# program_counter.net
KiCad netlist of a schematic drawn in Altium Designer
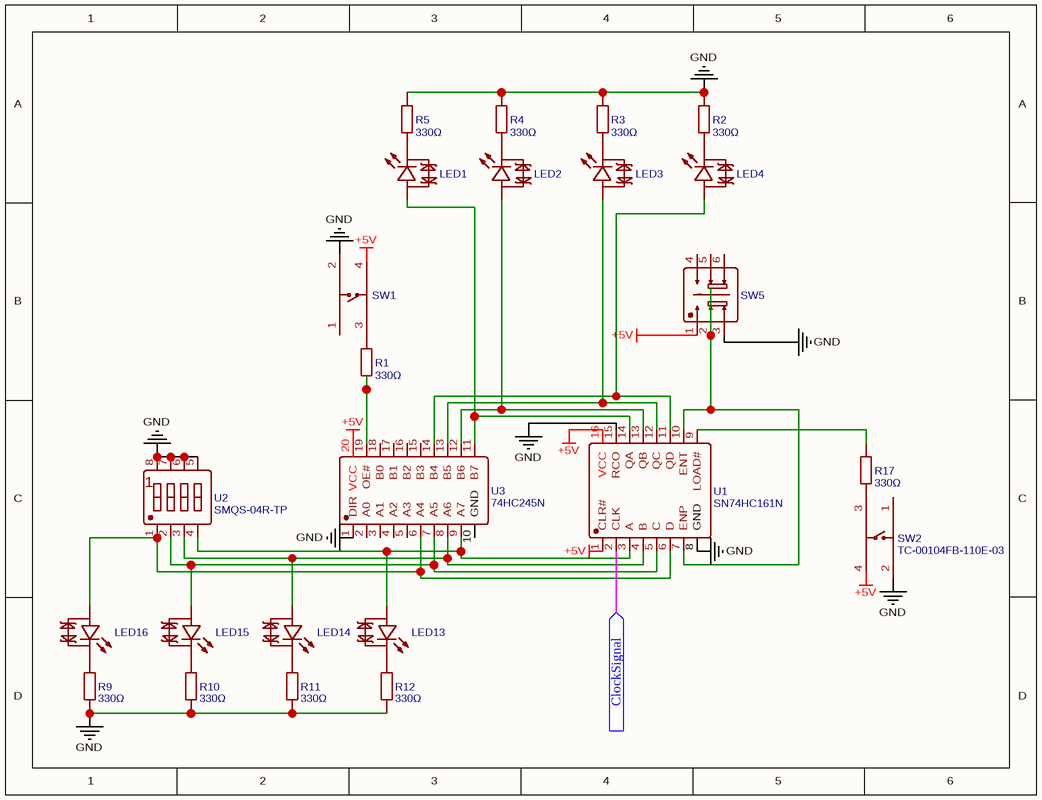
[diagram p0: program_counter.schdoc]

(export (version "E")
  (design (tool "Eeschema 10.0.6"))
  (components
    (comp (ref "LED1")
      (value "204-15UTC/S400-X9-L")
      (fields (field (name "MANUFACTURER") "EVERLIGHT(亿光)") (field (name "CONTRIBUTOR") "LCSC"))
      (libsource (lib "altium-import") (part "root_1_204-15UTC/S400-X9-L_"))
    )
    (comp (ref "LED2")
      (value "204-15UTC/S400-X9-L")
      (fields (field (name "MANUFACTURER") "EVERLIGHT(亿光)") (field (name "CONTRIBUTOR") "LCSC"))
      (libsource (lib "altium-import") (part "root_1_204-15UTC/S400-X9-L_"))
    )
    (comp (ref "LED3")
      (value "204-15UTC/S400-X9-L")
      (fields (field (name "MANUFACTURER") "EVERLIGHT(亿光)") (field (name "CONTRIBUTOR") "LCSC"))
      (libsource (lib "altium-import") (part "root_1_204-15UTC/S400-X9-L_"))
    )
    (comp (ref "LED4")
      (value "204-15UTC/S400-X9-L")
      (fields (field (name "MANUFACTURER") "EVERLIGHT(亿光)") (field (name "CONTRIBUTOR") "LCSC"))
      (libsource (lib "altium-import") (part "root_1_204-15UTC/S400-X9-L_"))
    )
    (comp (ref "LED13")
      (value "204-15UTC/S400-X9-L")
      (fields (field (name "MANUFACTURER") "EVERLIGHT(亿光)") (field (name "CONTRIBUTOR") "LCSC"))
      (libsource (lib "altium-import") (part "root_3_204-15UTC/S400-X9-L_"))
    )
    (comp (ref "LED14")
      (value "204-15UTC/S400-X9-L")
      (fields (field (name "MANUFACTURER") "EVERLIGHT(亿光)") (field (name "CONTRIBUTOR") "LCSC"))
      (libsource (lib "altium-import") (part "root_3_204-15UTC/S400-X9-L_"))
    )
    (comp (ref "LED15")
      (value "204-15UTC/S400-X9-L")
      (fields (field (name "MANUFACTURER") "EVERLIGHT(亿光)") (field (name "CONTRIBUTOR") "LCSC"))
      (libsource (lib "altium-import") (part "root_3_204-15UTC/S400-X9-L_"))
    )
    (comp (ref "LED16")
      (value "204-15UTC/S400-X9-L")
      (fields (field (name "MANUFACTURER") "EVERLIGHT(亿光)") (field (name "CONTRIBUTOR") "LCSC"))
      (libsource (lib "altium-import") (part "root_3_204-15UTC/S400-X9-L_"))
    )
    (comp (ref "R1")
      (value "330Ω")
      (fields
        (field (name "MANUFACTURER") "CCO(千志电子)")
        (field (name "MANUFACTURER PART") "MF1/2W-0.1Ω±1% T")
        (field (name "CONTRIBUTOR") "LCSC")
      )
      (libsource (lib "altium-import") (part "root_1_330Ω_"))
    )
    (comp (ref "R2")
      (value "330Ω")
      (fields
        (field (name "MANUFACTURER") "CCO(千志电子)")
        (field (name "MANUFACTURER PART") "MF1/2W-0.1Ω±1% T")
        (field (name "CONTRIBUTOR") "LCSC")
      )
      (libsource (lib "altium-import") (part "root_1_330Ω_"))
    )
    (comp (ref "R3")
      (value "330Ω")
      (fields
        (field (name "MANUFACTURER") "CCO(千志电子)")
        (field (name "MANUFACTURER PART") "MF1/2W-0.1Ω±1% T")
        (field (name "CONTRIBUTOR") "LCSC")
      )
      (libsource (lib "altium-import") (part "root_1_330Ω_"))
    )
    (comp (ref "R4")
      (value "330Ω")
      (fields
        (field (name "MANUFACTURER") "CCO(千志电子)")
        (field (name "MANUFACTURER PART") "MF1/2W-0.1Ω±1% T")
        (field (name "CONTRIBUTOR") "LCSC")
      )
      (libsource (lib "altium-import") (part "root_1_330Ω_"))
    )
    (comp (ref "R5")
      (value "330Ω")
      (fields
        (field (name "MANUFACTURER") "CCO(千志电子)")
        (field (name "MANUFACTURER PART") "MF1/2W-0.1Ω±1% T")
        (field (name "CONTRIBUTOR") "LCSC")
      )
      (libsource (lib "altium-import") (part "root_1_330Ω_"))
    )
    (comp (ref "R9")
      (value "330Ω")
      (fields
        (field (name "MANUFACTURER") "CCO(千志电子)")
        (field (name "MANUFACTURER PART") "MF1/2W-0.1Ω±1% T")
        (field (name "CONTRIBUTOR") "LCSC")
      )
      (libsource (lib "altium-import") (part "root_3_330Ω_"))
    )
    (comp (ref "R10")
      (value "330Ω")
      (fields
        (field (name "MANUFACTURER") "CCO(千志电子)")
        (field (name "MANUFACTURER PART") "MF1/2W-0.1Ω±1% T")
        (field (name "CONTRIBUTOR") "LCSC")
      )
      (libsource (lib "altium-import") (part "root_3_330Ω_"))
    )
    (comp (ref "R11")
      (value "330Ω")
      (fields
        (field (name "MANUFACTURER") "CCO(千志电子)")
        (field (name "MANUFACTURER PART") "MF1/2W-0.1Ω±1% T")
        (field (name "CONTRIBUTOR") "LCSC")
      )
      (libsource (lib "altium-import") (part "root_3_330Ω_"))
    )
    (comp (ref "R12")
      (value "330Ω")
      (fields
        (field (name "MANUFACTURER") "CCO(千志电子)")
        (field (name "MANUFACTURER PART") "MF1/2W-0.1Ω±1% T")
        (field (name "CONTRIBUTOR") "LCSC")
      )
      (libsource (lib "altium-import") (part "root_3_330Ω_"))
    )
    (comp (ref "R17")
      (value "330Ω")
      (fields
        (field (name "MANUFACTURER") "CCO(千志电子)")
        (field (name "MANUFACTURER PART") "MF1/2W-0.1Ω±1% T")
        (field (name "CONTRIBUTOR") "LCSC")
      )
      (libsource (lib "altium-import") (part "root_3_330Ω_"))
    )
    (comp (ref "SW1")
      (value "TC-00104FB-110E-03")
      (fields (field (name "MANUFACTURER") "HOOYA(皓宇电子)") (field (name "CONTRIBUTOR") "lcsc"))
      (libsource (lib "altium-import") (part "root_1_TC-00104FB-110E-03_"))
    )
    (comp (ref "SW2")
      (value "TC-00104FB-110E-03")
      (fields (field (name "MANUFACTURER") "HOOYA(皓宇电子)") (field (name "CONTRIBUTOR") "lcsc"))
      (libsource (lib "altium-import") (part "root_3_TC-00104FB-110E-03_"))
    )
    (comp (ref "SW5")
      (value "XKB8585-Z-190")
      (fields (field (name "MANUFACTURER") "XKB Connectivity(中国星坤)") (field (name "CONTRIBUTOR") "LCSC"))
      (libsource (lib "altium-import") (part "root_1_XKB8585-Z-190_"))
    )
    (comp (ref "U1")
      (value "SN74HC161N")
      (fields (field (name "MANUFACTURER") "TI(德州仪器)") (field (name "CONTRIBUTOR") "lcsc"))
      (libsource (lib "altium-import") (part "root_1_SN74HC161N_"))
    )
    (comp (ref "U2")
      (value "SMQS-04R-TP")
      (fields (field (name "MANUFACTURER") "SM Switch") (field (name "CONTRIBUTOR") "lcsc"))
      (libsource (lib "altium-import") (part "root_1_SMQS-04R-TP_"))
    )
    (comp (ref "U3")
      (value "74HC245N")
      (fields (field (name "MANUFACTURER") "HGSEMI(华冠)") (field (name "CONTRIBUTOR") "LCSC"))
      (libsource (lib "altium-import") (part "root_1_74HC245N_"))
    )
  )
  (nets
    (net (code "1") (name "+5V") (class "Default")
      (node (ref "SW5") (pin "1") (pinfunction "1_1") (pintype "passive"))
      (node (ref "U1") (pin "1") (pinfunction "CLR#_1") (pintype "passive"))
      (node (ref "U1") (pin "16") (pinfunction "VCC_16") (pintype "passive"))
      (node (ref "U3") (pin "20") (pinfunction "VCC_20") (pintype "passive"))
    )
    (net (code "2") (name "/ClockSignal") (class "Default")
      (node (ref "U1") (pin "2") (pinfunction "CLK_2") (pintype "passive"))
    )
    (net (code "3") (name "GND") (class "Default")
      (node (ref "R10") (pin "2") (pinfunction "2_2") (pintype "passive"))
      (node (ref "R11") (pin "2") (pinfunction "2_2") (pintype "passive"))
      (node (ref "R12") (pin "2") (pinfunction "2_2") (pintype "passive"))
      (node (ref "R2") (pin "2") (pinfunction "2_2") (pintype "passive"))
      (node (ref "R3") (pin "2") (pinfunction "2_2") (pintype "passive"))
      (node (ref "R4") (pin "2") (pinfunction "2_2") (pintype "passive"))
      (node (ref "R5") (pin "2") (pinfunction "2_2") (pintype "passive"))
      (node (ref "R9") (pin "2") (pinfunction "2_2") (pintype "passive"))
      (node (ref "SW1") (pin "2") (pinfunction "2_2") (pintype "passive"))
      (node (ref "SW2") (pin "2") (pinfunction "2_2") (pintype "passive"))
      (node (ref "SW5") (pin "3") (pinfunction "3_3") (pintype "passive"))
      (node (ref "U1") (pin "15") (pinfunction "RCO_15") (pintype "passive"))
      (node (ref "U1") (pin "8") (pinfunction "GND_8") (pintype "passive"))
      (node (ref "U2") (pin "5") (pinfunction "PIN5_5") (pintype "passive"))
      (node (ref "U2") (pin "6") (pinfunction "PIN6_6") (pintype "passive"))
      (node (ref "U2") (pin "7") (pinfunction "PIN7_7") (pintype "passive"))
      (node (ref "U2") (pin "8") (pinfunction "PIN8_8") (pintype "passive"))
      (node (ref "U3") (pin "1") (pinfunction "DIR_1") (pintype "passive"))
    )
    (net (code "4") (name "Net-(LED1-A)") (class "Default")
      (node (ref "LED1") (pin "1") (pinfunction "A_1") (pintype "passive"))
      (node (ref "U1") (pin "14") (pinfunction "QA_14") (pintype "passive"))
      (node (ref "U3") (pin "11") (pinfunction "B7_11") (pintype "passive"))
    )
    (net (code "5") (name "Net-(LED1-C)") (class "Default")
      (node (ref "LED1") (pin "2") (pinfunction "C_2") (pintype "passive"))
      (node (ref "R5") (pin "1") (pinfunction "1_1") (pintype "passive"))
    )
    (net (code "6") (name "Net-(LED2-A)") (class "Default")
      (node (ref "LED2") (pin "1") (pinfunction "A_1") (pintype "passive"))
      (node (ref "U1") (pin "13") (pinfunction "QB_13") (pintype "passive"))
      (node (ref "U3") (pin "12") (pinfunction "B6_12") (pintype "passive"))
    )
    (net (code "7") (name "Net-(LED2-C)") (class "Default")
      (node (ref "LED2") (pin "2") (pinfunction "C_2") (pintype "passive"))
      (node (ref "R4") (pin "1") (pinfunction "1_1") (pintype "passive"))
    )
    (net (code "8") (name "Net-(LED3-A)") (class "Default")
      (node (ref "LED3") (pin "1") (pinfunction "A_1") (pintype "passive"))
      (node (ref "U1") (pin "12") (pinfunction "QC_12") (pintype "passive"))
      (node (ref "U3") (pin "13") (pinfunction "B5_13") (pintype "passive"))
    )
    (net (code "9") (name "Net-(LED3-C)") (class "Default")
      (node (ref "LED3") (pin "2") (pinfunction "C_2") (pintype "passive"))
      (node (ref "R3") (pin "1") (pinfunction "1_1") (pintype "passive"))
    )
    (net (code "10") (name "Net-(LED4-A)") (class "Default")
      (node (ref "LED4") (pin "1") (pinfunction "A_1") (pintype "passive"))
      (node (ref "U1") (pin "11") (pinfunction "QD_11") (pintype "passive"))
      (node (ref "U3") (pin "14") (pinfunction "B4_14") (pintype "passive"))
    )
    (net (code "11") (name "Net-(LED4-C)") (class "Default")
      (node (ref "LED4") (pin "2") (pinfunction "C_2") (pintype "passive"))
      (node (ref "R2") (pin "1") (pinfunction "1_1") (pintype "passive"))
    )
    (net (code "12") (name "Net-(LED13-A)") (class "Default")
      (node (ref "LED13") (pin "1") (pinfunction "A_1") (pintype "passive"))
      (node (ref "U1") (pin "3") (pinfunction "A_3") (pintype "passive"))
      (node (ref "U2") (pin "4") (pinfunction "PIN4_4") (pintype "passive"))
      (node (ref "U3") (pin "9") (pinfunction "A7_9") (pintype "passive"))
    )
    (net (code "13") (name "Net-(LED13-C)") (class "Default")
      (node (ref "LED13") (pin "2") (pinfunction "C_2") (pintype "passive"))
      (node (ref "R12") (pin "1") (pinfunction "1_1") (pintype "passive"))
    )
    (net (code "14") (name "Net-(LED14-A)") (class "Default")
      (node (ref "LED14") (pin "1") (pinfunction "A_1") (pintype "passive"))
      (node (ref "U1") (pin "4") (pinfunction "B_4") (pintype "passive"))
      (node (ref "U2") (pin "3") (pinfunction "PIN3_3") (pintype "passive"))
      (node (ref "U3") (pin "8") (pinfunction "A6_8") (pintype "passive"))
    )
    (net (code "15") (name "Net-(LED14-C)") (class "Default")
      (node (ref "LED14") (pin "2") (pinfunction "C_2") (pintype "passive"))
      (node (ref "R11") (pin "1") (pinfunction "1_1") (pintype "passive"))
    )
    (net (code "16") (name "Net-(LED15-A)") (class "Default")
      (node (ref "LED15") (pin "1") (pinfunction "A_1") (pintype "passive"))
      (node (ref "U1") (pin "5") (pinfunction "C_5") (pintype "passive"))
      (node (ref "U2") (pin "2") (pinfunction "PIN2_2") (pintype "passive"))
      (node (ref "U3") (pin "7") (pinfunction "A5_7") (pintype "passive"))
    )
    (net (code "17") (name "Net-(LED15-C)") (class "Default")
      (node (ref "LED15") (pin "2") (pinfunction "C_2") (pintype "passive"))
      (node (ref "R10") (pin "1") (pinfunction "1_1") (pintype "passive"))
    )
    (net (code "18") (name "Net-(LED16-A)") (class "Default")
      (node (ref "LED16") (pin "1") (pinfunction "A_1") (pintype "passive"))
      (node (ref "U1") (pin "6") (pinfunction "D_6") (pintype "passive"))
      (node (ref "U2") (pin "1") (pinfunction "PIN1_1") (pintype "passive"))
      (node (ref "U3") (pin "6") (pinfunction "A4_6") (pintype "passive"))
    )
    (net (code "19") (name "Net-(LED16-C)") (class "Default")
      (node (ref "LED16") (pin "2") (pinfunction "C_2") (pintype "passive"))
      (node (ref "R9") (pin "1") (pinfunction "1_1") (pintype "passive"))
    )
    (net (code "20") (name "Net-(R1-Pad2)") (class "Default")
      (node (ref "R1") (pin "2") (pinfunction "2_2") (pintype "passive"))
      (node (ref "SW1") (pin "3") (pinfunction "3_3") (pintype "passive"))
    )
    (net (code "21") (name "Net-(R17-Pad2)") (class "Default")
      (node (ref "R17") (pin "2") (pinfunction "2_2") (pintype "passive"))
      (node (ref "SW2") (pin "3") (pinfunction "3_3") (pintype "passive"))
    )
    (net (code "22") (name "Net-(U1-ENP)") (class "Default")
      (node (ref "SW5") (pin "2") (pinfunction "2_2") (pintype "passive"))
      (node (ref "U1") (pin "10") (pinfunction "ENT_10") (pintype "passive"))
      (node (ref "U1") (pin "7") (pinfunction "ENP_7") (pintype "passive"))
    )
    (net (code "23") (name "Net-(U1-LOAD#)") (class "Default")
      (node (ref "R17") (pin "1") (pinfunction "1_1") (pintype "passive"))
      (node (ref "U1") (pin "9") (pinfunction "LOAD#_9") (pintype "passive"))
    )
    (net (code "24") (name "Net-(U3-OE#)") (class "Default")
      (node (ref "R1") (pin "1") (pinfunction "1_1") (pintype "passive"))
      (node (ref "U3") (pin "19") (pinfunction "OE#_19") (pintype "passive"))
    )
    (net (code "25") (name "unconnected-(SW1-Pad1)") (class "Default")
      (node (ref "SW1") (pin "1") (pinfunction "1_1") (pintype "passive"))
    )
    (net (code "26") (name "unconnected-(SW1-Pad4)") (class "Default")
      (node (ref "SW1") (pin "4") (pinfunction "4_4") (pintype "passive"))
    )
    (net (code "27") (name "unconnected-(SW2-Pad1)") (class "Default")
      (node (ref "SW2") (pin "1") (pinfunction "1_1") (pintype "passive"))
    )
    (net (code "28") (name "unconnected-(SW2-Pad4)") (class "Default")
      (node (ref "SW2") (pin "4") (pinfunction "4_4") (pintype "passive"))
    )
    (net (code "29") (name "unconnected-(SW5-Pad4)") (class "Default")
      (node (ref "SW5") (pin "4") (pinfunction "4_4") (pintype "passive"))
    )
    (net (code "30") (name "unconnected-(SW5-Pad5)") (class "Default")
      (node (ref "SW5") (pin "5") (pinfunction "5_5") (pintype "passive"))
    )
    (net (code "31") (name "unconnected-(SW5-Pad6)") (class "Default")
      (node (ref "SW5") (pin "6") (pinfunction "6_6") (pintype "passive"))
    )
    (net (code "32") (name "unconnected-(U3-A0-Pad2)") (class "Default")
      (node (ref "U3") (pin "2") (pinfunction "A0_2") (pintype "passive"))
    )
    (net (code "33") (name "unconnected-(U3-A1-Pad3)") (class "Default")
      (node (ref "U3") (pin "3") (pinfunction "A1_3") (pintype "passive"))
    )
    (net (code "34") (name "unconnected-(U3-A2-Pad4)") (class "Default")
      (node (ref "U3") (pin "4") (pinfunction "A2_4") (pintype "passive"))
    )
    (net (code "35") (name "unconnected-(U3-A3-Pad5)") (class "Default")
      (node (ref "U3") (pin "5") (pinfunction "A3_5") (pintype "passive"))
    )
    (net (code "36") (name "unconnected-(U3-B0-Pad18)") (class "Default")
      (node (ref "U3") (pin "18") (pinfunction "B0_18") (pintype "passive"))
    )
    (net (code "37") (name "unconnected-(U3-B1-Pad17)") (class "Default")
      (node (ref "U3") (pin "17") (pinfunction "B1_17") (pintype "passive"))
    )
    (net (code "38") (name "unconnected-(U3-B2-Pad16)") (class "Default")
      (node (ref "U3") (pin "16") (pinfunction "B2_16") (pintype "passive"))
    )
    (net (code "39") (name "unconnected-(U3-B3-Pad15)") (class "Default")
      (node (ref "U3") (pin "15") (pinfunction "B3_15") (pintype "passive"))
    )
    (net (code "40") (name "unconnected-(U3-GND-Pad10)") (class "Default")
      (node (ref "U3") (pin "10") (pinfunction "GND_10") (pintype "passive"))
    )
  )
)
